# LightSensitiveDCPower.net
KiCad netlist of a schematic drawn in EAGLE
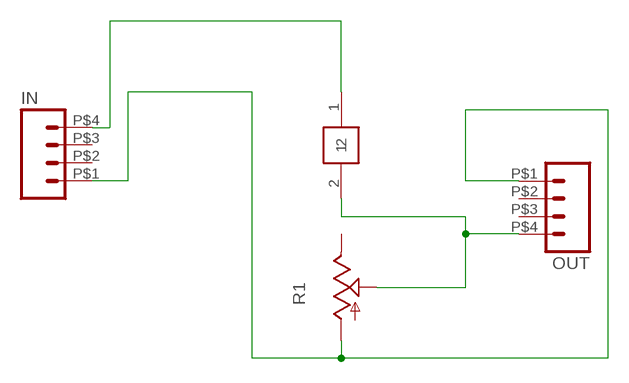
[diagram p0: schematic, sheet 1]

(export (version "E")
  (design (tool "Eeschema 10.0.6"))
  (components
    (comp (ref "IN")
      (value "M04HORIZ_PTH")
      (footprint "eagle-import:SULLIN-1X4_HORIZ")
      (libsource (lib "eagle-import") (part "M04HORIZ_PTH"))
    )
    (comp (ref "OUT")
      (value "M04HORIZ_PTH")
      (footprint "eagle-import:SULLIN-1X4_HORIZ")
      (libsource (lib "eagle-import") (part "M04HORIZ_PTH"))
    )
    (comp (ref "PC1")
      (value "PDV-P8101")
      (footprint "eagle-import:PHOTOCELL_CERAMIC")
      (libsource (lib "eagle-import") (part "PDV-P8101"))
    )
    (comp (ref "R1")
      (value "TRIM_US-B25P")
      (footprint "eagle-import:B25P")
      (libsource (lib "eagle-import") (part "TRIM_US-B25P"))
    )
  )
  (nets
    (net (code "1") (name "Net-(IN-1)") (class "Default")
      (node (ref "IN") (pin "P$1") (pinfunction "1_P$1") (pintype "passive"))
      (node (ref "OUT") (pin "P$1") (pinfunction "1_P$1") (pintype "passive"))
      (node (ref "R1") (pin "A") (pinfunction "A_A") (pintype "passive"))
    )
    (net (code "2") (name "Net-(IN-4)") (class "Default")
      (node (ref "IN") (pin "P$4") (pinfunction "4_P$4") (pintype "passive"))
      (node (ref "PC1") (pin "1") (pinfunction "1_1") (pintype "bidirectional"))
    )
    (net (code "3") (name "Net-(OUT-4)") (class "Default")
      (node (ref "OUT") (pin "P$4") (pinfunction "4_P$4") (pintype "passive"))
      (node (ref "PC1") (pin "2") (pinfunction "2_2") (pintype "bidirectional"))
      (node (ref "R1") (pin "S") (pinfunction "S_S") (pintype "passive"))
    )
    (net (code "4") (name "unconnected-(IN-2-PadP$2)") (class "Default")
      (node (ref "IN") (pin "P$2") (pinfunction "2_P$2") (pintype "passive"))
    )
    (net (code "5") (name "unconnected-(IN-3-PadP$3)") (class "Default")
      (node (ref "IN") (pin "P$3") (pinfunction "3_P$3") (pintype "passive"))
    )
    (net (code "6") (name "unconnected-(OUT-2-PadP$2)") (class "Default")
      (node (ref "OUT") (pin "P$2") (pinfunction "2_P$2") (pintype "passive"))
    )
    (net (code "7") (name "unconnected-(OUT-3-PadP$3)") (class "Default")
      (node (ref "OUT") (pin "P$3") (pinfunction "3_P$3") (pintype "passive"))
    )
    (net (code "8") (name "unconnected-(R1-PadE)") (class "Default")
      (node (ref "R1") (pin "E") (pinfunction "E_E") (pintype "passive"))
    )
  )
)
